# GROUP_09.net
KiCad netlist of a schematic drawn in EAGLE
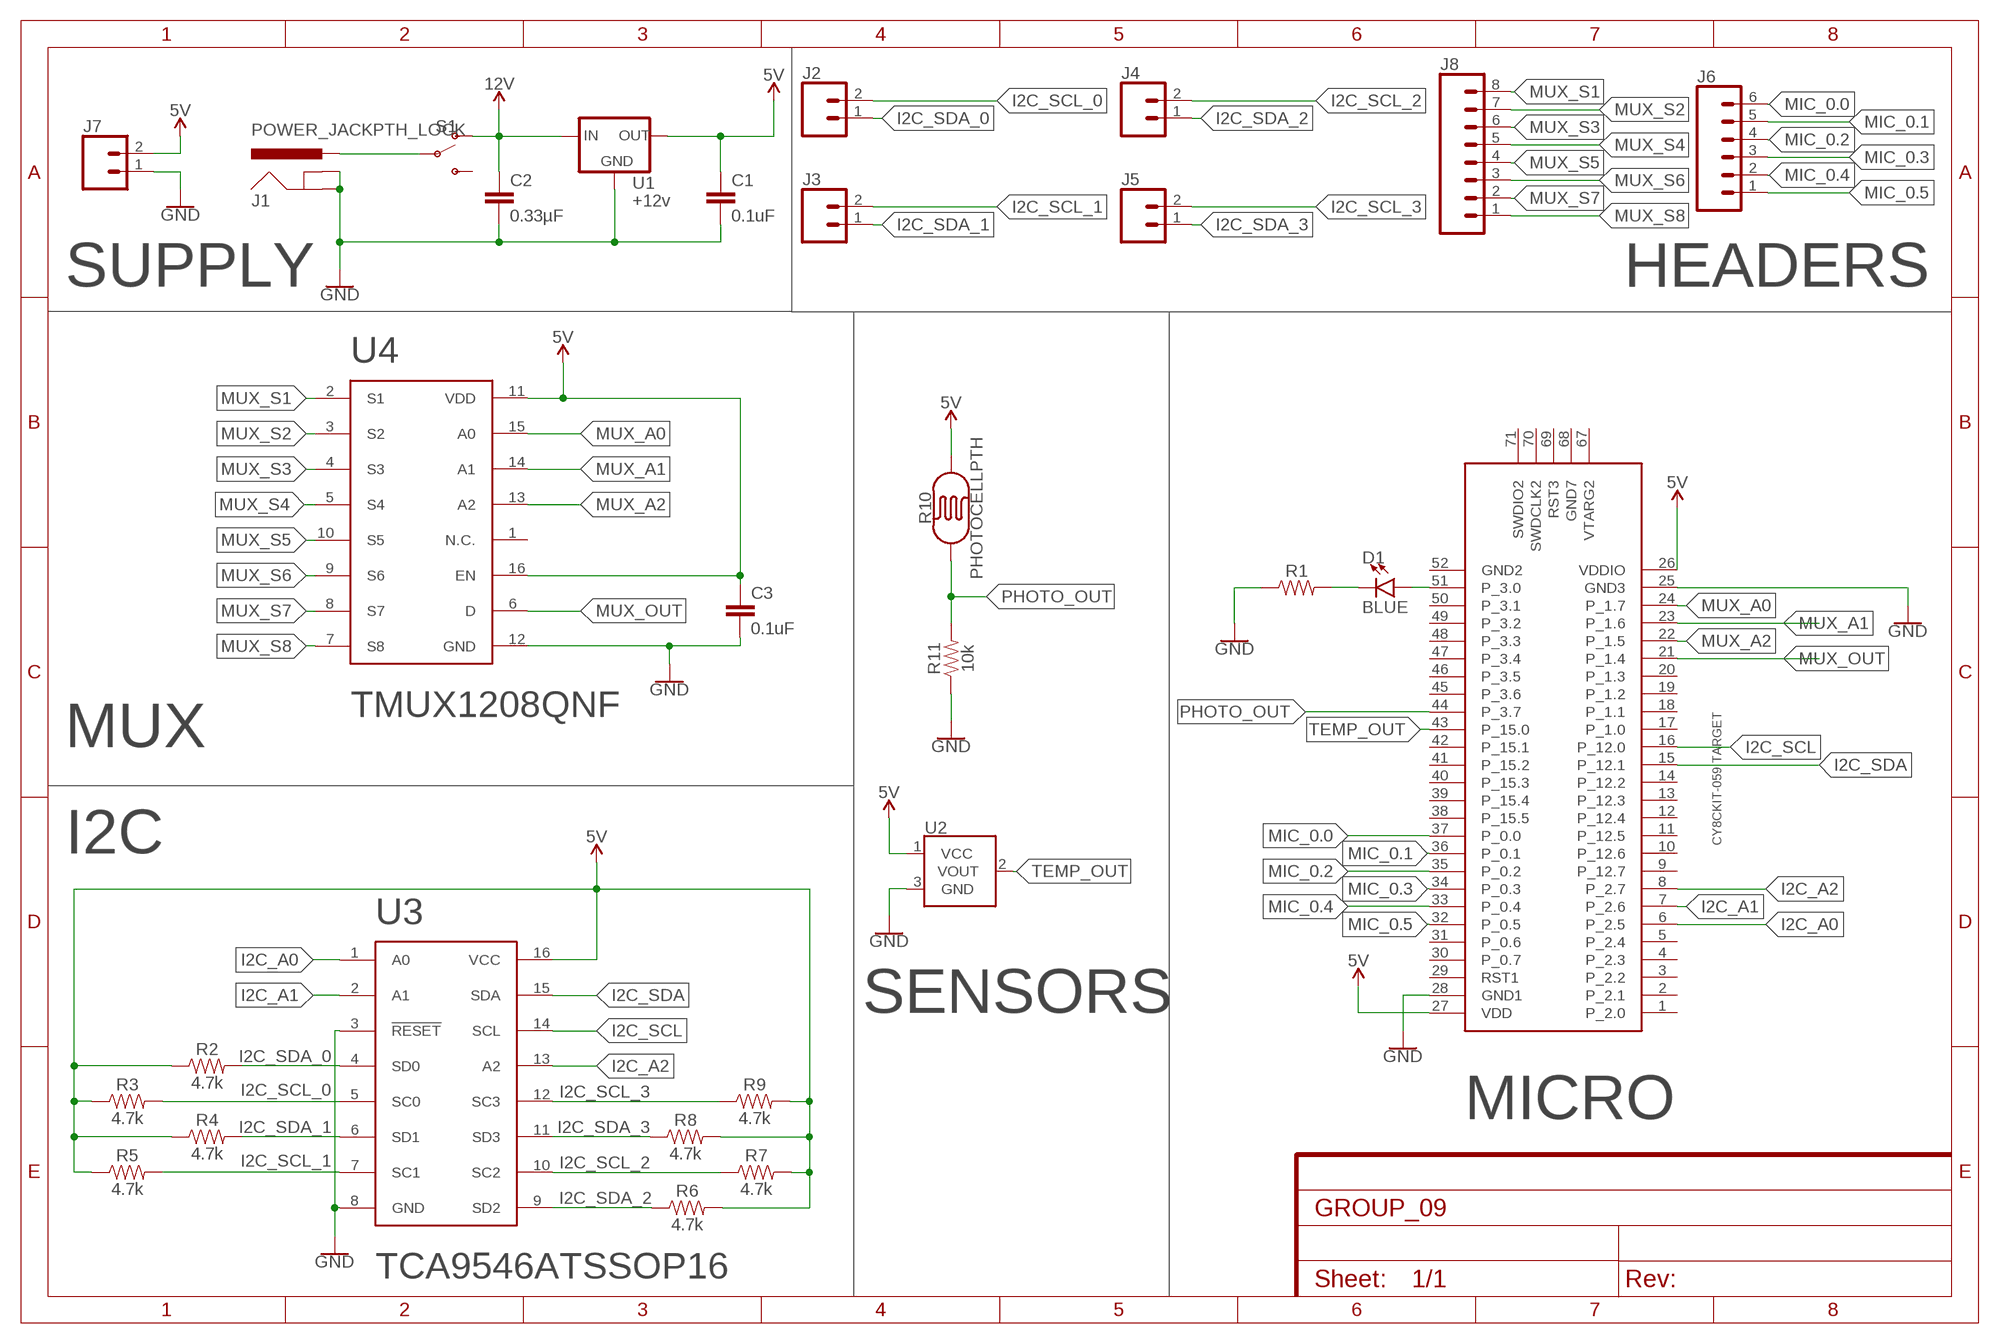
[diagram p0: schematic, sheet 1]

(export (version "E")
  (design (tool "Eeschema 10.0.6"))
  (components
    (comp (ref "C1")
      (value "0.1uF")
      (footprint "eagle-import:CAP-PTH-SMALL-KIT")
      (libsource (lib "eagle-import") (part "0.1UF-KIT-EZ-50V-20%"))
    )
    (comp (ref "C2")
      (value "0.33µF")
      (footprint "eagle-import:0805")
      (libsource (lib "eagle-import") (part "0.33UF/330NF-0805-50V-10%"))
    )
    (comp (ref "C3")
      (value "0.1uF")
      (footprint "eagle-import:CAP-PTH-SMALL-KIT")
      (libsource (lib "eagle-import") (part "0.1UF-KIT-EZ-50V-20%"))
    )
    (comp (ref "CY8CKIT059-TARGET")
      (value "CY8CKIT-059_TARGET")
      (footprint "eagle-import:CY8CKIT-059_TARGET")
      (libsource (lib "eagle-import") (part "CY8CKIT-059_TARGET"))
    )
    (comp (ref "D1")
      (value "BLUE")
      (footprint "eagle-import:LED-1206")
      (libsource (lib "eagle-import") (part "LED-BLUE1206"))
    )
    (comp (ref "J1")
      (value "POWER_JACKPTH_LOCK")
      (footprint "eagle-import:POWER_JACK_PTH_LOCK")
      (libsource (lib "eagle-import") (part "POWER_JACKPTH_LOCK"))
    )
    (comp (ref "J2")
      (value "CONN_02")
      (footprint "eagle-import:1X02")
      (libsource (lib "eagle-import") (part "CONN_02"))
    )
    (comp (ref "J3")
      (value "CONN_02")
      (footprint "eagle-import:1X02")
      (libsource (lib "eagle-import") (part "CONN_02"))
    )
    (comp (ref "J4")
      (value "CONN_02")
      (footprint "eagle-import:1X02")
      (libsource (lib "eagle-import") (part "CONN_02"))
    )
    (comp (ref "J5")
      (value "CONN_02")
      (footprint "eagle-import:1X02")
      (libsource (lib "eagle-import") (part "CONN_02"))
    )
    (comp (ref "J6")
      (value "CONN_06LOCK")
      (footprint "eagle-import:1X06_LOCK")
      (libsource (lib "eagle-import") (part "CONN_06LOCK"))
    )
    (comp (ref "J7")
      (value "CONN_02")
      (footprint "eagle-import:1X02")
      (libsource (lib "eagle-import") (part "CONN_02"))
    )
    (comp (ref "J8")
      (value "CONN_08LOCK")
      (footprint "eagle-import:1X08_LOCK")
      (libsource (lib "eagle-import") (part "CONN_08LOCK"))
    )
    (comp (ref "R1")
      (value "RESISTORAXIAL-0.3")
      (footprint "eagle-import:AXIAL-0.3")
      (libsource (lib "eagle-import") (part "RESISTORAXIAL-0.3"))
    )
    (comp (ref "R2")
      (value "4.7k")
      (footprint "eagle-import:0603")
      (libsource (lib "eagle-import") (part "4.7KOHM-0603-1/10W-1%"))
    )
    (comp (ref "R3")
      (value "4.7k")
      (footprint "eagle-import:0603")
      (libsource (lib "eagle-import") (part "4.7KOHM-0603-1/10W-1%"))
    )
    (comp (ref "R4")
      (value "4.7k")
      (footprint "eagle-import:0603")
      (libsource (lib "eagle-import") (part "4.7KOHM-0603-1/10W-1%"))
    )
    (comp (ref "R5")
      (value "4.7k")
      (footprint "eagle-import:0603")
      (libsource (lib "eagle-import") (part "4.7KOHM-0603-1/10W-1%"))
    )
    (comp (ref "R6")
      (value "4.7k")
      (footprint "eagle-import:0603")
      (libsource (lib "eagle-import") (part "4.7KOHM-0603-1/10W-1%"))
    )
    (comp (ref "R7")
      (value "4.7k")
      (footprint "eagle-import:0603")
      (libsource (lib "eagle-import") (part "4.7KOHM-0603-1/10W-1%"))
    )
    (comp (ref "R8")
      (value "4.7k")
      (footprint "eagle-import:0603")
      (libsource (lib "eagle-import") (part "4.7KOHM-0603-1/10W-1%"))
    )
    (comp (ref "R9")
      (value "4.7k")
      (footprint "eagle-import:0603")
      (libsource (lib "eagle-import") (part "4.7KOHM-0603-1/10W-1%"))
    )
    (comp (ref "R10")
      (value "PHOTOCELLPTH")
      (footprint "eagle-import:PHOTOCELL")
      (libsource (lib "eagle-import") (part "PHOTOCELLPTH"))
    )
    (comp (ref "R11")
      (value "10k")
      (footprint "eagle-import:0603")
      (libsource (lib "eagle-import") (part "10KOHM-0603-1/10W-1%"))
    )
    (comp (ref "S1")
      (value "SWITCH-SPDT-PTH-11.6X4.0MM")
      (footprint "eagle-import:SWITCH_SPDT_PTH_11.6X4.0MM")
      (libsource (lib "eagle-import") (part "SWITCH-SPDT-PTH-11.6X4.0MM"))
    )
    (comp (ref "U1")
      (value "+12v")
      (footprint "eagle-import:TO-252")
      (libsource (lib "eagle-import") (part "V_REG_78XX7812"))
    )
    (comp (ref "U2")
      (value "TMP36GT9")
      (footprint "eagle-import:TO-92")
      (libsource (lib "eagle-import") (part "TMP36GT9"))
    )
    (comp (ref "U3")
      (value "TCA9546ATSSOP16")
      (footprint "eagle-import:TSSOP-16")
      (libsource (lib "eagle-import") (part "TCA9546ATSSOP16"))
    )
    (comp (ref "U4")
      (value "TMUX1208QNF")
      (footprint "eagle-import:QFN-16")
      (libsource (lib "eagle-import") (part "TMUX1208QNF"))
    )
  )
  (nets
    (net (code "1") (name "5V") (class "Default")
      (node (ref "C1") (pin "1") (pinfunction "1_1") (pintype "passive"))
      (node (ref "C3") (pin "1") (pinfunction "1_1") (pintype "passive"))
      (node (ref "CY8CKIT059-TARGET") (pin "26") (pinfunction "VDDIO_26") (pintype "bidirectional"))
      (node (ref "CY8CKIT059-TARGET") (pin "27") (pinfunction "VDD_27") (pintype "bidirectional"))
      (node (ref "J7") (pin "2") (pinfunction "2_2") (pintype "passive"))
      (node (ref "R10") (pin "2") (pinfunction "P$2_2") (pintype "bidirectional"))
      (node (ref "R2") (pin "1") (pinfunction "1_1") (pintype "passive"))
      (node (ref "R3") (pin "1") (pinfunction "1_1") (pintype "passive"))
      (node (ref "R4") (pin "1") (pinfunction "1_1") (pintype "passive"))
      (node (ref "R5") (pin "1") (pinfunction "1_1") (pintype "passive"))
      (node (ref "R6") (pin "2") (pinfunction "2_2") (pintype "passive"))
      (node (ref "R7") (pin "2") (pinfunction "2_2") (pintype "passive"))
      (node (ref "R8") (pin "2") (pinfunction "2_2") (pintype "passive"))
      (node (ref "R9") (pin "2") (pinfunction "2_2") (pintype "passive"))
      (node (ref "U1") (pin "2") (pinfunction "OUT_2") (pintype "passive"))
      (node (ref "U2") (pin "1") (pinfunction "VCC_1") (pintype "bidirectional"))
      (node (ref "U3") (pin "16") (pinfunction "VCC_16") (pintype "bidirectional"))
      (node (ref "U4") (pin "11") (pinfunction "VDD_11") (pintype "bidirectional"))
      (node (ref "U4") (pin "16") (pinfunction "EN_16") (pintype "bidirectional"))
    )
    (net (code "2") (name "12V") (class "Default")
      (node (ref "C2") (pin "1") (pinfunction "1_1") (pintype "passive"))
      (node (ref "S1") (pin "1") (pinfunction "O_1") (pintype "passive"))
      (node (ref "U1") (pin "1") (pinfunction "IN_1") (pintype "input"))
    )
    (net (code "3") (name "GND") (class "Default")
      (node (ref "C1") (pin "2") (pinfunction "2_2") (pintype "passive"))
      (node (ref "C2") (pin "2") (pinfunction "2_2") (pintype "passive"))
      (node (ref "C3") (pin "2") (pinfunction "2_2") (pintype "passive"))
      (node (ref "CY8CKIT059-TARGET") (pin "25") (pinfunction "GND3_25") (pintype "bidirectional"))
      (node (ref "CY8CKIT059-TARGET") (pin "28") (pinfunction "GND1_28") (pintype "bidirectional"))
      (node (ref "J1") (pin "GND") (pinfunction "GND_GND") (pintype "bidirectional"))
      (node (ref "J1") (pin "GNDBREAK") (pinfunction "GNDBREAK_GNDBREAK") (pintype "bidirectional"))
      (node (ref "J7") (pin "1") (pinfunction "1_1") (pintype "passive"))
      (node (ref "R1") (pin "P$1") (pinfunction "1_P$1") (pintype "passive"))
      (node (ref "R11") (pin "1") (pinfunction "1_1") (pintype "passive"))
      (node (ref "U1") (pin "3") (pinfunction "GND_3") (pintype "input"))
      (node (ref "U2") (pin "3") (pinfunction "GND_3") (pintype "bidirectional"))
      (node (ref "U3") (pin "3") (pinfunction "~{RESET}_3") (pintype "bidirectional"))
      (node (ref "U3") (pin "8") (pinfunction "GND_8") (pintype "bidirectional"))
      (node (ref "U4") (pin "12") (pinfunction "GND_12") (pintype "bidirectional"))
    )
    (net (code "4") (name "I2C_A0") (class "Default")
      (node (ref "CY8CKIT059-TARGET") (pin "6") (pinfunction "P_2.5_6") (pintype "bidirectional"))
      (node (ref "U3") (pin "1") (pinfunction "A0_1") (pintype "bidirectional"))
    )
    (net (code "5") (name "I2C_A1") (class "Default")
      (node (ref "CY8CKIT059-TARGET") (pin "7") (pinfunction "P_2.6_7") (pintype "bidirectional"))
      (node (ref "U3") (pin "2") (pinfunction "A1_2") (pintype "bidirectional"))
    )
    (net (code "6") (name "I2C_A2") (class "Default")
      (node (ref "CY8CKIT059-TARGET") (pin "8") (pinfunction "P_2.7_8") (pintype "bidirectional"))
      (node (ref "U3") (pin "13") (pinfunction "A2_13") (pintype "bidirectional"))
    )
    (net (code "7") (name "I2C_SCL") (class "Default")
      (node (ref "CY8CKIT059-TARGET") (pin "16") (pinfunction "P_12.0_16") (pintype "bidirectional"))
      (node (ref "U3") (pin "14") (pinfunction "SCL_14") (pintype "bidirectional"))
    )
    (net (code "8") (name "I2C_SCL_0") (class "Default")
      (node (ref "J2") (pin "2") (pinfunction "2_2") (pintype "passive"))
      (node (ref "R3") (pin "2") (pinfunction "2_2") (pintype "passive"))
      (node (ref "U3") (pin "5") (pinfunction "SC0_5") (pintype "bidirectional"))
    )
    (net (code "9") (name "I2C_SCL_1") (class "Default")
      (node (ref "J3") (pin "2") (pinfunction "2_2") (pintype "passive"))
      (node (ref "R5") (pin "2") (pinfunction "2_2") (pintype "passive"))
      (node (ref "U3") (pin "7") (pinfunction "SC1_7") (pintype "bidirectional"))
    )
    (net (code "10") (name "I2C_SCL_2") (class "Default")
      (node (ref "J4") (pin "2") (pinfunction "2_2") (pintype "passive"))
      (node (ref "R7") (pin "1") (pinfunction "1_1") (pintype "passive"))
      (node (ref "U3") (pin "10") (pinfunction "SC2_10") (pintype "bidirectional"))
    )
    (net (code "11") (name "I2C_SCL_3") (class "Default")
      (node (ref "J5") (pin "2") (pinfunction "2_2") (pintype "passive"))
      (node (ref "R9") (pin "1") (pinfunction "1_1") (pintype "passive"))
      (node (ref "U3") (pin "12") (pinfunction "SC3_12") (pintype "bidirectional"))
    )
    (net (code "12") (name "I2C_SDA") (class "Default")
      (node (ref "CY8CKIT059-TARGET") (pin "15") (pinfunction "P_12.1_15") (pintype "bidirectional"))
      (node (ref "U3") (pin "15") (pinfunction "SDA_15") (pintype "bidirectional"))
    )
    (net (code "13") (name "I2C_SDA_0") (class "Default")
      (node (ref "J2") (pin "1") (pinfunction "1_1") (pintype "passive"))
      (node (ref "R2") (pin "2") (pinfunction "2_2") (pintype "passive"))
      (node (ref "U3") (pin "4") (pinfunction "SD0_4") (pintype "bidirectional"))
    )
    (net (code "14") (name "I2C_SDA_1") (class "Default")
      (node (ref "J3") (pin "1") (pinfunction "1_1") (pintype "passive"))
      (node (ref "R4") (pin "2") (pinfunction "2_2") (pintype "passive"))
      (node (ref "U3") (pin "6") (pinfunction "SD1_6") (pintype "bidirectional"))
    )
    (net (code "15") (name "I2C_SDA_2") (class "Default")
      (node (ref "J4") (pin "1") (pinfunction "1_1") (pintype "passive"))
      (node (ref "R6") (pin "1") (pinfunction "1_1") (pintype "passive"))
      (node (ref "U3") (pin "9") (pinfunction "SD2_9") (pintype "bidirectional"))
    )
    (net (code "16") (name "I2C_SDA_3") (class "Default")
      (node (ref "J5") (pin "1") (pinfunction "1_1") (pintype "passive"))
      (node (ref "R8") (pin "1") (pinfunction "1_1") (pintype "passive"))
      (node (ref "U3") (pin "11") (pinfunction "SD3_11") (pintype "bidirectional"))
    )
    (net (code "17") (name "MIC_0.0") (class "Default")
      (node (ref "CY8CKIT059-TARGET") (pin "37") (pinfunction "P_0.0_37") (pintype "bidirectional"))
      (node (ref "J6") (pin "6") (pinfunction "6_6") (pintype "passive"))
    )
    (net (code "18") (name "MIC_0.1") (class "Default")
      (node (ref "CY8CKIT059-TARGET") (pin "36") (pinfunction "P_0.1_36") (pintype "bidirectional"))
      (node (ref "J6") (pin "5") (pinfunction "5_5") (pintype "passive"))
    )
    (net (code "19") (name "MIC_0.2") (class "Default")
      (node (ref "CY8CKIT059-TARGET") (pin "35") (pinfunction "P_0.2_35") (pintype "bidirectional"))
      (node (ref "J6") (pin "4") (pinfunction "4_4") (pintype "passive"))
    )
    (net (code "20") (name "MIC_0.3") (class "Default")
      (node (ref "CY8CKIT059-TARGET") (pin "34") (pinfunction "P_0.3_34") (pintype "bidirectional"))
      (node (ref "J6") (pin "3") (pinfunction "3_3") (pintype "passive"))
    )
    (net (code "21") (name "MIC_0.4") (class "Default")
      (node (ref "CY8CKIT059-TARGET") (pin "33") (pinfunction "P_0.4_33") (pintype "bidirectional"))
      (node (ref "J6") (pin "2") (pinfunction "2_2") (pintype "passive"))
    )
    (net (code "22") (name "MIC_0.5") (class "Default")
      (node (ref "CY8CKIT059-TARGET") (pin "32") (pinfunction "P_0.5_32") (pintype "bidirectional"))
      (node (ref "J6") (pin "1") (pinfunction "1_1") (pintype "passive"))
    )
    (net (code "23") (name "MUX_A0") (class "Default")
      (node (ref "CY8CKIT059-TARGET") (pin "24") (pinfunction "P_1.7_24") (pintype "bidirectional"))
      (node (ref "U4") (pin "15") (pinfunction "A0_15") (pintype "bidirectional"))
    )
    (net (code "24") (name "MUX_A1") (class "Default")
      (node (ref "CY8CKIT059-TARGET") (pin "23") (pinfunction "P_1.6_23") (pintype "bidirectional"))
      (node (ref "U4") (pin "14") (pinfunction "A1_14") (pintype "bidirectional"))
    )
    (net (code "25") (name "MUX_A2") (class "Default")
      (node (ref "CY8CKIT059-TARGET") (pin "22") (pinfunction "P_1.5_22") (pintype "bidirectional"))
      (node (ref "U4") (pin "13") (pinfunction "A2_13") (pintype "bidirectional"))
    )
    (net (code "26") (name "MUX_OUT") (class "Default")
      (node (ref "CY8CKIT059-TARGET") (pin "21") (pinfunction "P_1.4_21") (pintype "bidirectional"))
      (node (ref "U4") (pin "6") (pinfunction "D_6") (pintype "bidirectional"))
    )
    (net (code "27") (name "MUX_S1") (class "Default")
      (node (ref "J8") (pin "8") (pinfunction "8_8") (pintype "passive"))
      (node (ref "U4") (pin "2") (pinfunction "S1_2") (pintype "bidirectional"))
    )
    (net (code "28") (name "MUX_S2") (class "Default")
      (node (ref "J8") (pin "7") (pinfunction "7_7") (pintype "passive"))
      (node (ref "U4") (pin "3") (pinfunction "S2_3") (pintype "bidirectional"))
    )
    (net (code "29") (name "MUX_S3") (class "Default")
      (node (ref "J8") (pin "6") (pinfunction "6_6") (pintype "passive"))
      (node (ref "U4") (pin "4") (pinfunction "S3_4") (pintype "bidirectional"))
    )
    (net (code "30") (name "MUX_S4") (class "Default")
      (node (ref "J8") (pin "5") (pinfunction "5_5") (pintype "passive"))
      (node (ref "U4") (pin "5") (pinfunction "S4_5") (pintype "bidirectional"))
    )
    (net (code "31") (name "MUX_S5") (class "Default")
      (node (ref "J8") (pin "4") (pinfunction "4_4") (pintype "passive"))
      (node (ref "U4") (pin "10") (pinfunction "S5_10") (pintype "bidirectional"))
    )
    (net (code "32") (name "MUX_S6") (class "Default")
      (node (ref "J8") (pin "3") (pinfunction "3_3") (pintype "passive"))
      (node (ref "U4") (pin "9") (pinfunction "S6_9") (pintype "bidirectional"))
    )
    (net (code "33") (name "MUX_S7") (class "Default")
      (node (ref "J8") (pin "2") (pinfunction "2_2") (pintype "passive"))
      (node (ref "U4") (pin "8") (pinfunction "S7_8") (pintype "bidirectional"))
    )
    (net (code "34") (name "MUX_S8") (class "Default")
      (node (ref "J8") (pin "1") (pinfunction "1_1") (pintype "passive"))
      (node (ref "U4") (pin "7") (pinfunction "S8_7") (pintype "bidirectional"))
    )
    (net (code "35") (name "Net-(CY8CKIT059-TARGET-P_3.0)") (class "Default")
      (node (ref "CY8CKIT059-TARGET") (pin "51") (pinfunction "P_3.0_51") (pintype "bidirectional"))
      (node (ref "D1") (pin "A") (pinfunction "A_A") (pintype "passive"))
    )
    (net (code "36") (name "Net-(R1-2)") (class "Default")
      (node (ref "D1") (pin "C") (pinfunction "C_C") (pintype "passive"))
      (node (ref "R1") (pin "P$2") (pinfunction "2_P$2") (pintype "passive"))
    )
    (net (code "37") (name "Net-(S1-P)") (class "Default")
      (node (ref "J1") (pin "PWR") (pinfunction "PWR_PWR") (pintype "bidirectional"))
      (node (ref "S1") (pin "2") (pinfunction "P_2") (pintype "passive"))
    )
    (net (code "38") (name "PHOTO_OUT") (class "Default")
      (node (ref "CY8CKIT059-TARGET") (pin "44") (pinfunction "P_3.7_44") (pintype "bidirectional"))
      (node (ref "R10") (pin "1") (pinfunction "P$1_1") (pintype "bidirectional"))
      (node (ref "R11") (pin "2") (pinfunction "2_2") (pintype "passive"))
    )
    (net (code "39") (name "TEMP_OUT") (class "Default")
      (node (ref "CY8CKIT059-TARGET") (pin "43") (pinfunction "P_15.0_43") (pintype "bidirectional"))
      (node (ref "U2") (pin "2") (pinfunction "VOUT_2") (pintype "bidirectional"))
    )
    (net (code "40") (name "unconnected-(CY8CKIT059-TARGET-GND2-Pad52)") (class "Default")
      (node (ref "CY8CKIT059-TARGET") (pin "52") (pinfunction "GND2_52") (pintype "bidirectional"))
    )
    (net (code "41") (name "unconnected-(CY8CKIT059-TARGET-GND7-Pad68)") (class "Default")
      (node (ref "CY8CKIT059-TARGET") (pin "68") (pinfunction "GND7_68") (pintype "bidirectional"))
    )
    (net (code "42") (name "unconnected-(CY8CKIT059-TARGET-P_0.6-Pad31)") (class "Default")
      (node (ref "CY8CKIT059-TARGET") (pin "31") (pinfunction "P_0.6_31") (pintype "bidirectional"))
    )
    (net (code "43") (name "unconnected-(CY8CKIT059-TARGET-P_0.7-Pad30)") (class "Default")
      (node (ref "CY8CKIT059-TARGET") (pin "30") (pinfunction "P_0.7_30") (pintype "bidirectional"))
    )
    (net (code "44") (name "unconnected-(CY8CKIT059-TARGET-P_1.0-Pad17)") (class "Default")
      (node (ref "CY8CKIT059-TARGET") (pin "17") (pinfunction "P_1.0_17") (pintype "bidirectional"))
    )
    (net (code "45") (name "unconnected-(CY8CKIT059-TARGET-P_1.1-Pad18)") (class "Default")
      (node (ref "CY8CKIT059-TARGET") (pin "18") (pinfunction "P_1.1_18") (pintype "bidirectional"))
    )
    (net (code "46") (name "unconnected-(CY8CKIT059-TARGET-P_1.2-Pad19)") (class "Default")
      (node (ref "CY8CKIT059-TARGET") (pin "19") (pinfunction "P_1.2_19") (pintype "bidirectional"))
    )
    (net (code "47") (name "unconnected-(CY8CKIT059-TARGET-P_1.3-Pad20)") (class "Default")
      (node (ref "CY8CKIT059-TARGET") (pin "20") (pinfunction "P_1.3_20") (pintype "bidirectional"))
    )
    (net (code "48") (name "unconnected-(CY8CKIT059-TARGET-P_2.0-Pad1)") (class "Default")
      (node (ref "CY8CKIT059-TARGET") (pin "1") (pinfunction "P_2.0_1") (pintype "bidirectional"))
    )
    (net (code "49") (name "unconnected-(CY8CKIT059-TARGET-P_2.1-Pad2)") (class "Default")
      (node (ref "CY8CKIT059-TARGET") (pin "2") (pinfunction "P_2.1_2") (pintype "bidirectional"))
    )
    (net (code "50") (name "unconnected-(CY8CKIT059-TARGET-P_2.2-Pad3)") (class "Default")
      (node (ref "CY8CKIT059-TARGET") (pin "3") (pinfunction "P_2.2_3") (pintype "bidirectional"))
    )
    (net (code "51") (name "unconnected-(CY8CKIT059-TARGET-P_2.3-Pad4)") (class "Default")
      (node (ref "CY8CKIT059-TARGET") (pin "4") (pinfunction "P_2.3_4") (pintype "bidirectional"))
    )
    (net (code "52") (name "unconnected-(CY8CKIT059-TARGET-P_2.4-Pad5)") (class "Default")
      (node (ref "CY8CKIT059-TARGET") (pin "5") (pinfunction "P_2.4_5") (pintype "bidirectional"))
    )
    (net (code "53") (name "unconnected-(CY8CKIT059-TARGET-P_3.1-Pad50)") (class "Default")
      (node (ref "CY8CKIT059-TARGET") (pin "50") (pinfunction "P_3.1_50") (pintype "bidirectional"))
    )
    (net (code "54") (name "unconnected-(CY8CKIT059-TARGET-P_3.2-Pad49)") (class "Default")
      (node (ref "CY8CKIT059-TARGET") (pin "49") (pinfunction "P_3.2_49") (pintype "bidirectional"))
    )
    (net (code "55") (name "unconnected-(CY8CKIT059-TARGET-P_3.3-Pad48)") (class "Default")
      (node (ref "CY8CKIT059-TARGET") (pin "48") (pinfunction "P_3.3_48") (pintype "bidirectional"))
    )
    (net (code "56") (name "unconnected-(CY8CKIT059-TARGET-P_3.4-Pad47)") (class "Default")
      (node (ref "CY8CKIT059-TARGET") (pin "47") (pinfunction "P_3.4_47") (pintype "bidirectional"))
    )
    (net (code "57") (name "unconnected-(CY8CKIT059-TARGET-P_3.5-Pad46)") (class "Default")
      (node (ref "CY8CKIT059-TARGET") (pin "46") (pinfunction "P_3.5_46") (pintype "bidirectional"))
    )
    (net (code "58") (name "unconnected-(CY8CKIT059-TARGET-P_3.6-Pad45)") (class "Default")
      (node (ref "CY8CKIT059-TARGET") (pin "45") (pinfunction "P_3.6_45") (pintype "bidirectional"))
    )
    (net (code "59") (name "unconnected-(CY8CKIT059-TARGET-P_12.2-Pad14)") (class "Default")
      (node (ref "CY8CKIT059-TARGET") (pin "14") (pinfunction "P_12.2_14") (pintype "bidirectional"))
    )
    (net (code "60") (name "unconnected-(CY8CKIT059-TARGET-P_12.3-Pad13)") (class "Default")
      (node (ref "CY8CKIT059-TARGET") (pin "13") (pinfunction "P_12.3_13") (pintype "bidirectional"))
    )
    (net (code "61") (name "unconnected-(CY8CKIT059-TARGET-P_12.4-Pad12)") (class "Default")
      (node (ref "CY8CKIT059-TARGET") (pin "12") (pinfunction "P_12.4_12") (pintype "bidirectional"))
    )
    (net (code "62") (name "unconnected-(CY8CKIT059-TARGET-P_12.5-Pad11)") (class "Default")
      (node (ref "CY8CKIT059-TARGET") (pin "11") (pinfunction "P_12.5_11") (pintype "bidirectional"))
    )
    (net (code "63") (name "unconnected-(CY8CKIT059-TARGET-P_12.6-Pad10)") (class "Default")
      (node (ref "CY8CKIT059-TARGET") (pin "10") (pinfunction "P_12.6_10") (pintype "bidirectional"))
    )
    (net (code "64") (name "unconnected-(CY8CKIT059-TARGET-P_12.7-Pad9)") (class "Default")
      (node (ref "CY8CKIT059-TARGET") (pin "9") (pinfunction "P_12.7_9") (pintype "bidirectional"))
    )
    (net (code "65") (name "unconnected-(CY8CKIT059-TARGET-P_15.1-Pad42)") (class "Default")
      (node (ref "CY8CKIT059-TARGET") (pin "42") (pinfunction "P_15.1_42") (pintype "bidirectional"))
    )
    (net (code "66") (name "unconnected-(CY8CKIT059-TARGET-P_15.2-Pad41)") (class "Default")
      (node (ref "CY8CKIT059-TARGET") (pin "41") (pinfunction "P_15.2_41") (pintype "bidirectional"))
    )
    (net (code "67") (name "unconnected-(CY8CKIT059-TARGET-P_15.3-Pad40)") (class "Default")
      (node (ref "CY8CKIT059-TARGET") (pin "40") (pinfunction "P_15.3_40") (pintype "bidirectional"))
    )
    (net (code "68") (name "unconnected-(CY8CKIT059-TARGET-P_15.4-Pad39)") (class "Default")
      (node (ref "CY8CKIT059-TARGET") (pin "39") (pinfunction "P_15.4_39") (pintype "bidirectional"))
    )
    (net (code "69") (name "unconnected-(CY8CKIT059-TARGET-P_15.5-Pad38)") (class "Default")
      (node (ref "CY8CKIT059-TARGET") (pin "38") (pinfunction "P_15.5_38") (pintype "bidirectional"))
    )
    (net (code "70") (name "unconnected-(CY8CKIT059-TARGET-RST1-Pad29)") (class "Default")
      (node (ref "CY8CKIT059-TARGET") (pin "29") (pinfunction "RST1_29") (pintype "bidirectional"))
    )
    (net (code "71") (name "unconnected-(CY8CKIT059-TARGET-RST3-Pad69)") (class "Default")
      (node (ref "CY8CKIT059-TARGET") (pin "69") (pinfunction "RST3_69") (pintype "bidirectional"))
    )
    (net (code "72") (name "unconnected-(CY8CKIT059-TARGET-SWDCLK2-Pad70)") (class "Default")
      (node (ref "CY8CKIT059-TARGET") (pin "70") (pinfunction "SWDCLK2_70") (pintype "bidirectional"))
    )
    (net (code "73") (name "unconnected-(CY8CKIT059-TARGET-SWDIO2-Pad71)") (class "Default")
      (node (ref "CY8CKIT059-TARGET") (pin "71") (pinfunction "SWDIO2_71") (pintype "bidirectional"))
    )
    (net (code "74") (name "unconnected-(CY8CKIT059-TARGET-VTARG2-Pad67)") (class "Default")
      (node (ref "CY8CKIT059-TARGET") (pin "67") (pinfunction "VTARG2_67") (pintype "bidirectional"))
    )
    (net (code "75") (name "unconnected-(S1-S-Pad3)") (class "Default")
      (node (ref "S1") (pin "3") (pinfunction "S_3") (pintype "passive"))
    )
    (net (code "76") (name "unconnected-(U4-N.C.-Pad1)") (class "Default")
      (node (ref "U4") (pin "1") (pinfunction "N.C._1") (pintype "bidirectional"))
    )
  )
)
